# ECE411GroupTwoWordClockV5.net
KiCad netlist of a schematic drawn in EAGLE
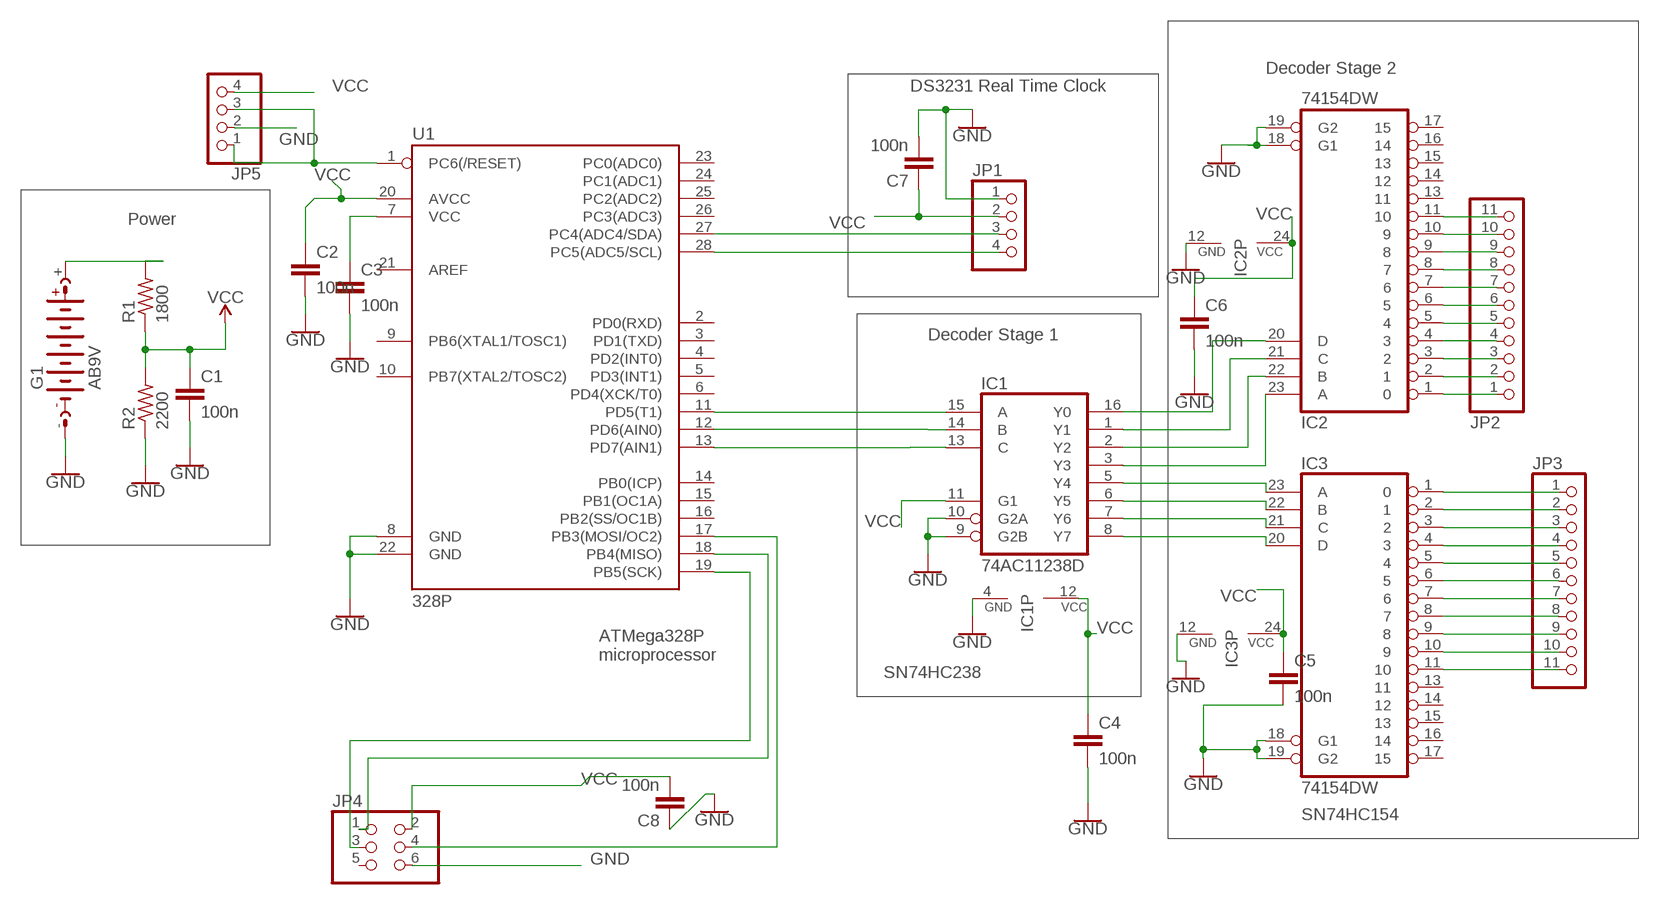
[diagram p0: schematic, sheet 1]

(export (version "E")
  (design (tool "Eeschema 10.0.6"))
  (components
    (comp (ref "C1")
      (value "100n")
      (footprint "eagle-import:C025-025X050")
      (libsource (lib "eagle-import") (part "C-EU025-025X050"))
    )
    (comp (ref "C2")
      (value "100n")
      (footprint "eagle-import:C025-025X050")
      (libsource (lib "eagle-import") (part "C-EU025-025X050"))
    )
    (comp (ref "C3")
      (value "100n")
      (footprint "eagle-import:C025-025X050")
      (libsource (lib "eagle-import") (part "C-EU025-025X050"))
    )
    (comp (ref "C4")
      (value "100n")
      (footprint "eagle-import:C025-025X050")
      (libsource (lib "eagle-import") (part "C-EU025-025X050"))
    )
    (comp (ref "C5")
      (value "100n")
      (footprint "eagle-import:C025-025X050")
      (libsource (lib "eagle-import") (part "C-EU025-025X050"))
    )
    (comp (ref "C6")
      (value "100n")
      (footprint "eagle-import:C025-025X050")
      (libsource (lib "eagle-import") (part "C-EU025-025X050"))
    )
    (comp (ref "C7")
      (value "100n")
      (footprint "eagle-import:C025-025X050")
      (libsource (lib "eagle-import") (part "C-EU025-025X050"))
    )
    (comp (ref "C8")
      (value "100n")
      (footprint "eagle-import:C025-025X050")
      (libsource (lib "eagle-import") (part "C-EU025-025X050"))
    )
    (comp (ref "G1")
      (value "AB9V")
      (footprint "eagle-import:AB9V")
      (libsource (lib "eagle-import") (part "AB9V"))
    )
    (comp (ref "IC1")
      (value "74AC11238D")
      (footprint "eagle-import:SO16")
      (libsource (lib "eagle-import") (part "74AC11238D"))
    )
    (comp (ref "IC2")
      (value "74154DW")
      (footprint "eagle-import:SO24W")
      (libsource (lib "eagle-import") (part "74154DW"))
    )
    (comp (ref "IC3")
      (value "74154DW")
      (footprint "eagle-import:SO24W")
      (libsource (lib "eagle-import") (part "74154DW"))
    )
    (comp (ref "JP1")
      (value "PINHD-1X4")
      (footprint "eagle-import:1X04")
      (libsource (lib "eagle-import") (part "PINHD-1X4"))
    )
    (comp (ref "JP2")
      (value "PINHD-1X11")
      (footprint "eagle-import:1X11")
      (libsource (lib "eagle-import") (part "PINHD-1X11"))
    )
    (comp (ref "JP3")
      (value "PINHD-1X11")
      (footprint "eagle-import:1X11")
      (libsource (lib "eagle-import") (part "PINHD-1X11"))
    )
    (comp (ref "JP4")
      (value "PINHD-2X3")
      (footprint "eagle-import:2X03")
      (libsource (lib "eagle-import") (part "PINHD-2X3"))
    )
    (comp (ref "JP5")
      (value "PINHD-1X4")
      (footprint "eagle-import:1X04")
      (libsource (lib "eagle-import") (part "PINHD-1X4"))
    )
    (comp (ref "R1")
      (value "1800")
      (footprint "eagle-import:0204V")
      (libsource (lib "eagle-import") (part "R-US_0204/2V"))
    )
    (comp (ref "R2")
      (value "2200")
      (footprint "eagle-import:0204V")
      (libsource (lib "eagle-import") (part "R-US_0204/2V"))
    )
    (comp (ref "U1")
      (value "328P")
      (footprint "eagle-import:DIP28")
      (libsource (lib "eagle-import") (part "ATMEGA328P_PDIP"))
    )
  )
  (nets
    (net (code "1") (name "GND") (class "Default")
      (node (ref "C1") (pin "2") (pinfunction "2_2") (pintype "passive"))
      (node (ref "C2") (pin "2") (pinfunction "2_2") (pintype "passive"))
      (node (ref "C3") (pin "2") (pinfunction "2_2") (pintype "passive"))
      (node (ref "C4") (pin "2") (pinfunction "2_2") (pintype "passive"))
      (node (ref "C5") (pin "2") (pinfunction "2_2") (pintype "passive"))
      (node (ref "C6") (pin "2") (pinfunction "2_2") (pintype "passive"))
      (node (ref "C7") (pin "2") (pinfunction "2_2") (pintype "passive"))
      (node (ref "C8") (pin "1") (pinfunction "1_1") (pintype "passive"))
      (node (ref "G1") (pin "-") (pinfunction "-_-") (pintype "passive"))
      (node (ref "IC1") (pin "10") (pinfunction "G2A_10") (pintype "input"))
      (node (ref "IC1") (pin "4") (pinfunction "GND_4") (pintype "power_in"))
      (node (ref "IC1") (pin "9") (pinfunction "G2B_9") (pintype "input"))
      (node (ref "IC2") (pin "12") (pinfunction "GND_12") (pintype "power_in"))
      (node (ref "IC2") (pin "18") (pinfunction "G1_18") (pintype "input"))
      (node (ref "IC2") (pin "19") (pinfunction "G2_19") (pintype "input"))
      (node (ref "IC3") (pin "12") (pinfunction "GND_12") (pintype "power_in"))
      (node (ref "IC3") (pin "18") (pinfunction "G1_18") (pintype "input"))
      (node (ref "IC3") (pin "19") (pinfunction "G2_19") (pintype "input"))
      (node (ref "JP1") (pin "1") (pinfunction "1_1") (pintype "passive"))
      (node (ref "JP4") (pin "6") (pinfunction "6_6") (pintype "passive"))
      (node (ref "JP5") (pin "2") (pinfunction "2_2") (pintype "passive"))
      (node (ref "R2") (pin "1") (pinfunction "1_1") (pintype "passive"))
      (node (ref "U1") (pin "22") (pinfunction "GND_22") (pintype "bidirectional"))
      (node (ref "U1") (pin "8") (pinfunction "GND_8") (pintype "bidirectional"))
    )
    (net (code "2") (name "Net-(G1-Pad+)") (class "Default")
      (node (ref "G1") (pin "+") (pinfunction "+_+") (pintype "passive"))
      (node (ref "R1") (pin "2") (pinfunction "2_2") (pintype "passive"))
    )
    (net (code "3") (name "Net-(IC1A-A)") (class "Default")
      (node (ref "IC1") (pin "15") (pinfunction "A_15") (pintype "input"))
      (node (ref "U1") (pin "11") (pinfunction "PD5(T1)_11") (pintype "bidirectional"))
    )
    (net (code "4") (name "Net-(IC1A-B)") (class "Default")
      (node (ref "IC1") (pin "14") (pinfunction "B_14") (pintype "input"))
      (node (ref "U1") (pin "12") (pinfunction "PD6(AIN0)_12") (pintype "bidirectional"))
    )
    (net (code "5") (name "Net-(IC1A-C)") (class "Default")
      (node (ref "IC1") (pin "13") (pinfunction "C_13") (pintype "input"))
      (node (ref "U1") (pin "13") (pinfunction "PD7(AIN1)_13") (pintype "bidirectional"))
    )
    (net (code "6") (name "Net-(IC1A-Y0)") (class "Default")
      (node (ref "IC1") (pin "16") (pinfunction "Y0_16") (pintype "output"))
      (node (ref "IC2") (pin "20") (pinfunction "D_20") (pintype "input"))
    )
    (net (code "7") (name "Net-(IC1A-Y1)") (class "Default")
      (node (ref "IC1") (pin "1") (pinfunction "Y1_1") (pintype "output"))
      (node (ref "IC2") (pin "21") (pinfunction "C_21") (pintype "input"))
    )
    (net (code "8") (name "Net-(IC1A-Y2)") (class "Default")
      (node (ref "IC1") (pin "2") (pinfunction "Y2_2") (pintype "output"))
      (node (ref "IC2") (pin "22") (pinfunction "B_22") (pintype "input"))
    )
    (net (code "9") (name "Net-(IC1A-Y3)") (class "Default")
      (node (ref "IC1") (pin "3") (pinfunction "Y3_3") (pintype "output"))
      (node (ref "IC2") (pin "23") (pinfunction "A_23") (pintype "input"))
    )
    (net (code "10") (name "Net-(IC1A-Y4)") (class "Default")
      (node (ref "IC1") (pin "5") (pinfunction "Y4_5") (pintype "output"))
      (node (ref "IC3") (pin "23") (pinfunction "A_23") (pintype "input"))
    )
    (net (code "11") (name "Net-(IC1A-Y5)") (class "Default")
      (node (ref "IC1") (pin "6") (pinfunction "Y5_6") (pintype "output"))
      (node (ref "IC3") (pin "22") (pinfunction "B_22") (pintype "input"))
    )
    (net (code "12") (name "Net-(IC1A-Y6)") (class "Default")
      (node (ref "IC1") (pin "7") (pinfunction "Y6_7") (pintype "output"))
      (node (ref "IC3") (pin "21") (pinfunction "C_21") (pintype "input"))
    )
    (net (code "13") (name "Net-(IC1A-Y7)") (class "Default")
      (node (ref "IC1") (pin "8") (pinfunction "Y7_8") (pintype "output"))
      (node (ref "IC3") (pin "20") (pinfunction "D_20") (pintype "input"))
    )
    (net (code "14") (name "Net-(IC2A-0)") (class "Default")
      (node (ref "IC2") (pin "1") (pinfunction "0_1") (pintype "output"))
      (node (ref "JP2") (pin "1") (pinfunction "1_1") (pintype "passive"))
    )
    (net (code "15") (name "Net-(IC2A-1)") (class "Default")
      (node (ref "IC2") (pin "2") (pinfunction "1_2") (pintype "output"))
      (node (ref "JP2") (pin "2") (pinfunction "2_2") (pintype "passive"))
    )
    (net (code "16") (name "Net-(IC2A-2)") (class "Default")
      (node (ref "IC2") (pin "3") (pinfunction "2_3") (pintype "output"))
      (node (ref "JP2") (pin "3") (pinfunction "3_3") (pintype "passive"))
    )
    (net (code "17") (name "Net-(IC2A-3)") (class "Default")
      (node (ref "IC2") (pin "4") (pinfunction "3_4") (pintype "output"))
      (node (ref "JP2") (pin "4") (pinfunction "4_4") (pintype "passive"))
    )
    (net (code "18") (name "Net-(IC2A-4)") (class "Default")
      (node (ref "IC2") (pin "5") (pinfunction "4_5") (pintype "output"))
      (node (ref "JP2") (pin "5") (pinfunction "5_5") (pintype "passive"))
    )
    (net (code "19") (name "Net-(IC2A-5)") (class "Default")
      (node (ref "IC2") (pin "6") (pinfunction "5_6") (pintype "output"))
      (node (ref "JP2") (pin "6") (pinfunction "6_6") (pintype "passive"))
    )
    (net (code "20") (name "Net-(IC2A-6)") (class "Default")
      (node (ref "IC2") (pin "7") (pinfunction "6_7") (pintype "output"))
      (node (ref "JP2") (pin "7") (pinfunction "7_7") (pintype "passive"))
    )
    (net (code "21") (name "Net-(IC2A-7)") (class "Default")
      (node (ref "IC2") (pin "8") (pinfunction "7_8") (pintype "output"))
      (node (ref "JP2") (pin "8") (pinfunction "8_8") (pintype "passive"))
    )
    (net (code "22") (name "Net-(IC2A-8)") (class "Default")
      (node (ref "IC2") (pin "9") (pinfunction "8_9") (pintype "output"))
      (node (ref "JP2") (pin "9") (pinfunction "9_9") (pintype "passive"))
    )
    (net (code "23") (name "Net-(IC2A-9)") (class "Default")
      (node (ref "IC2") (pin "10") (pinfunction "9_10") (pintype "output"))
      (node (ref "JP2") (pin "10") (pinfunction "10_10") (pintype "passive"))
    )
    (net (code "24") (name "Net-(IC2A-10)") (class "Default")
      (node (ref "IC2") (pin "11") (pinfunction "10_11") (pintype "output"))
      (node (ref "JP2") (pin "11") (pinfunction "11_11") (pintype "passive"))
    )
    (net (code "25") (name "Net-(IC3A-0)") (class "Default")
      (node (ref "IC3") (pin "1") (pinfunction "0_1") (pintype "output"))
      (node (ref "JP3") (pin "1") (pinfunction "1_1") (pintype "passive"))
    )
    (net (code "26") (name "Net-(IC3A-1)") (class "Default")
      (node (ref "IC3") (pin "2") (pinfunction "1_2") (pintype "output"))
      (node (ref "JP3") (pin "2") (pinfunction "2_2") (pintype "passive"))
    )
    (net (code "27") (name "Net-(IC3A-2)") (class "Default")
      (node (ref "IC3") (pin "3") (pinfunction "2_3") (pintype "output"))
      (node (ref "JP3") (pin "3") (pinfunction "3_3") (pintype "passive"))
    )
    (net (code "28") (name "Net-(IC3A-3)") (class "Default")
      (node (ref "IC3") (pin "4") (pinfunction "3_4") (pintype "output"))
      (node (ref "JP3") (pin "4") (pinfunction "4_4") (pintype "passive"))
    )
    (net (code "29") (name "Net-(IC3A-4)") (class "Default")
      (node (ref "IC3") (pin "5") (pinfunction "4_5") (pintype "output"))
      (node (ref "JP3") (pin "5") (pinfunction "5_5") (pintype "passive"))
    )
    (net (code "30") (name "Net-(IC3A-5)") (class "Default")
      (node (ref "IC3") (pin "6") (pinfunction "5_6") (pintype "output"))
      (node (ref "JP3") (pin "6") (pinfunction "6_6") (pintype "passive"))
    )
    (net (code "31") (name "Net-(IC3A-6)") (class "Default")
      (node (ref "IC3") (pin "7") (pinfunction "6_7") (pintype "output"))
      (node (ref "JP3") (pin "7") (pinfunction "7_7") (pintype "passive"))
    )
    (net (code "32") (name "Net-(IC3A-7)") (class "Default")
      (node (ref "IC3") (pin "8") (pinfunction "7_8") (pintype "output"))
      (node (ref "JP3") (pin "8") (pinfunction "8_8") (pintype "passive"))
    )
    (net (code "33") (name "Net-(IC3A-8)") (class "Default")
      (node (ref "IC3") (pin "9") (pinfunction "8_9") (pintype "output"))
      (node (ref "JP3") (pin "9") (pinfunction "9_9") (pintype "passive"))
    )
    (net (code "34") (name "Net-(IC3A-9)") (class "Default")
      (node (ref "IC3") (pin "10") (pinfunction "9_10") (pintype "output"))
      (node (ref "JP3") (pin "10") (pinfunction "10_10") (pintype "passive"))
    )
    (net (code "35") (name "Net-(IC3A-10)") (class "Default")
      (node (ref "IC3") (pin "11") (pinfunction "10_11") (pintype "output"))
      (node (ref "JP3") (pin "11") (pinfunction "11_11") (pintype "passive"))
    )
    (net (code "36") (name "Net-(U1-PB3(MOSI{slash}OC2))") (class "Default")
      (node (ref "JP4") (pin "4") (pinfunction "4_4") (pintype "passive"))
      (node (ref "U1") (pin "17") (pinfunction "PB3(MOSI/OC2)_17") (pintype "bidirectional"))
    )
    (net (code "37") (name "Net-(U1-PB4(MISO))") (class "Default")
      (node (ref "JP4") (pin "1") (pinfunction "1_1") (pintype "passive"))
      (node (ref "U1") (pin "18") (pinfunction "PB4(MISO)_18") (pintype "bidirectional"))
    )
    (net (code "38") (name "Net-(U1-PB5(SCK))") (class "Default")
      (node (ref "JP4") (pin "3") (pinfunction "3_3") (pintype "passive"))
      (node (ref "U1") (pin "19") (pinfunction "PB5(SCK)_19") (pintype "bidirectional"))
    )
    (net (code "39") (name "Net-(U1-PC4(ADC4{slash}SDA))") (class "Default")
      (node (ref "JP1") (pin "3") (pinfunction "3_3") (pintype "passive"))
      (node (ref "U1") (pin "27") (pinfunction "PC4(ADC4/SDA)_27") (pintype "bidirectional"))
    )
    (net (code "40") (name "Net-(U1-PC5(ADC5{slash}SCL))") (class "Default")
      (node (ref "JP1") (pin "4") (pinfunction "4_4") (pintype "passive"))
      (node (ref "U1") (pin "28") (pinfunction "PC5(ADC5/SCL)_28") (pintype "bidirectional"))
    )
    (net (code "41") (name "Net-(U1-PC6({slash}RESET))") (class "Default")
      (node (ref "JP5") (pin "1") (pinfunction "1_1") (pintype "passive"))
      (node (ref "JP5") (pin "3") (pinfunction "3_3") (pintype "passive"))
      (node (ref "U1") (pin "1") (pinfunction "PC6(/RESET)_1") (pintype "bidirectional"))
    )
    (net (code "42") (name "Net-(U1-VCC)") (class "Default")
      (node (ref "C3") (pin "1") (pinfunction "1_1") (pintype "passive"))
      (node (ref "U1") (pin "7") (pinfunction "VCC_7") (pintype "bidirectional"))
    )
    (net (code "43") (name "VCC") (class "Default")
      (node (ref "C1") (pin "1") (pinfunction "1_1") (pintype "passive"))
      (node (ref "C2") (pin "1") (pinfunction "1_1") (pintype "passive"))
      (node (ref "C4") (pin "1") (pinfunction "1_1") (pintype "passive"))
      (node (ref "C5") (pin "1") (pinfunction "1_1") (pintype "passive"))
      (node (ref "C6") (pin "1") (pinfunction "1_1") (pintype "passive"))
      (node (ref "C7") (pin "1") (pinfunction "1_1") (pintype "passive"))
      (node (ref "C8") (pin "2") (pinfunction "2_2") (pintype "passive"))
      (node (ref "IC1") (pin "11") (pinfunction "G1_11") (pintype "input"))
      (node (ref "IC1") (pin "12") (pinfunction "VCC_12") (pintype "power_in"))
      (node (ref "IC2") (pin "24") (pinfunction "VCC_24") (pintype "power_in"))
      (node (ref "IC3") (pin "24") (pinfunction "VCC_24") (pintype "power_in"))
      (node (ref "JP1") (pin "2") (pinfunction "2_2") (pintype "passive"))
      (node (ref "JP4") (pin "2") (pinfunction "2_2") (pintype "passive"))
      (node (ref "JP5") (pin "4") (pinfunction "4_4") (pintype "passive"))
      (node (ref "R1") (pin "1") (pinfunction "1_1") (pintype "passive"))
      (node (ref "R2") (pin "2") (pinfunction "2_2") (pintype "passive"))
      (node (ref "U1") (pin "20") (pinfunction "AVCC_20") (pintype "bidirectional"))
    )
    (net (code "44") (name "unconnected-(IC2A-11-Pad13)") (class "Default")
      (node (ref "IC2") (pin "13") (pinfunction "11_13") (pintype "output"))
    )
    (net (code "45") (name "unconnected-(IC2A-12-Pad14)") (class "Default")
      (node (ref "IC2") (pin "14") (pinfunction "12_14") (pintype "output"))
    )
    (net (code "46") (name "unconnected-(IC2A-13-Pad15)") (class "Default")
      (node (ref "IC2") (pin "15") (pinfunction "13_15") (pintype "output"))
    )
    (net (code "47") (name "unconnected-(IC2A-14-Pad16)") (class "Default")
      (node (ref "IC2") (pin "16") (pinfunction "14_16") (pintype "output"))
    )
    (net (code "48") (name "unconnected-(IC2A-15-Pad17)") (class "Default")
      (node (ref "IC2") (pin "17") (pinfunction "15_17") (pintype "output"))
    )
    (net (code "49") (name "unconnected-(IC3A-11-Pad13)") (class "Default")
      (node (ref "IC3") (pin "13") (pinfunction "11_13") (pintype "output"))
    )
    (net (code "50") (name "unconnected-(IC3A-12-Pad14)") (class "Default")
      (node (ref "IC3") (pin "14") (pinfunction "12_14") (pintype "output"))
    )
    (net (code "51") (name "unconnected-(IC3A-13-Pad15)") (class "Default")
      (node (ref "IC3") (pin "15") (pinfunction "13_15") (pintype "output"))
    )
    (net (code "52") (name "unconnected-(IC3A-14-Pad16)") (class "Default")
      (node (ref "IC3") (pin "16") (pinfunction "14_16") (pintype "output"))
    )
    (net (code "53") (name "unconnected-(IC3A-15-Pad17)") (class "Default")
      (node (ref "IC3") (pin "17") (pinfunction "15_17") (pintype "output"))
    )
    (net (code "54") (name "unconnected-(JP4-Pad5)") (class "Default")
      (node (ref "JP4") (pin "5") (pinfunction "5_5") (pintype "passive"))
    )
    (net (code "55") (name "unconnected-(U1-AREF-Pad21)") (class "Default")
      (node (ref "U1") (pin "21") (pinfunction "AREF_21") (pintype "bidirectional"))
    )
    (net (code "56") (name "unconnected-(U1-PB0(ICP)-Pad14)") (class "Default")
      (node (ref "U1") (pin "14") (pinfunction "PB0(ICP)_14") (pintype "bidirectional"))
    )
    (net (code "57") (name "unconnected-(U1-PB1(OC1A)-Pad15)") (class "Default")
      (node (ref "U1") (pin "15") (pinfunction "PB1(OC1A)_15") (pintype "bidirectional"))
    )
    (net (code "58") (name "unconnected-(U1-PB2(SS{slash}OC1B)-Pad16)") (class "Default")
      (node (ref "U1") (pin "16") (pinfunction "PB2(SS/OC1B)_16") (pintype "bidirectional"))
    )
    (net (code "59") (name "unconnected-(U1-PB6(XTAL1{slash}TOSC1)-Pad9)") (class "Default")
      (node (ref "U1") (pin "9") (pinfunction "PB6(XTAL1/TOSC1)_9") (pintype "bidirectional"))
    )
    (net (code "60") (name "unconnected-(U1-PB7(XTAL2{slash}TOSC2)-Pad10)") (class "Default")
      (node (ref "U1") (pin "10") (pinfunction "PB7(XTAL2/TOSC2)_10") (pintype "bidirectional"))
    )
    (net (code "61") (name "unconnected-(U1-PC0(ADC0)-Pad23)") (class "Default")
      (node (ref "U1") (pin "23") (pinfunction "PC0(ADC0)_23") (pintype "bidirectional"))
    )
    (net (code "62") (name "unconnected-(U1-PC1(ADC1)-Pad24)") (class "Default")
      (node (ref "U1") (pin "24") (pinfunction "PC1(ADC1)_24") (pintype "bidirectional"))
    )
    (net (code "63") (name "unconnected-(U1-PC2(ADC2)-Pad25)") (class "Default")
      (node (ref "U1") (pin "25") (pinfunction "PC2(ADC2)_25") (pintype "bidirectional"))
    )
    (net (code "64") (name "unconnected-(U1-PC3(ADC3)-Pad26)") (class "Default")
      (node (ref "U1") (pin "26") (pinfunction "PC3(ADC3)_26") (pintype "bidirectional"))
    )
    (net (code "65") (name "unconnected-(U1-PD0(RXD)-Pad2)") (class "Default")
      (node (ref "U1") (pin "2") (pinfunction "PD0(RXD)_2") (pintype "bidirectional"))
    )
    (net (code "66") (name "unconnected-(U1-PD1(TXD)-Pad3)") (class "Default")
      (node (ref "U1") (pin "3") (pinfunction "PD1(TXD)_3") (pintype "bidirectional"))
    )
    (net (code "67") (name "unconnected-(U1-PD2(INT0)-Pad4)") (class "Default")
      (node (ref "U1") (pin "4") (pinfunction "PD2(INT0)_4") (pintype "bidirectional"))
    )
    (net (code "68") (name "unconnected-(U1-PD3(INT1)-Pad5)") (class "Default")
      (node (ref "U1") (pin "5") (pinfunction "PD3(INT1)_5") (pintype "bidirectional"))
    )
    (net (code "69") (name "unconnected-(U1-PD4(XCK{slash}T0)-Pad6)") (class "Default")
      (node (ref "U1") (pin "6") (pinfunction "PD4(XCK/T0)_6") (pintype "bidirectional"))
    )
  )
)
